# kicker.net
KiCad netlist of a schematic drawn in EAGLE
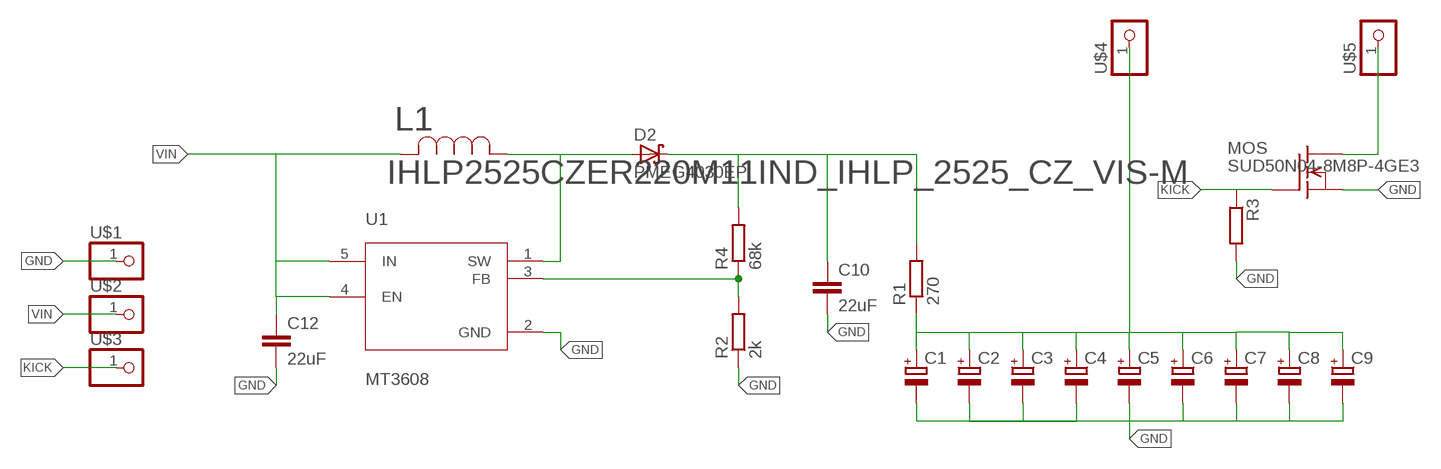
[diagram p0: schematic, sheet 1]

(export (version "E")
  (design (tool "Eeschema 10.0.6"))
  (components
    (comp (ref "C1")
      (value "CPOL-EU153CLV-1010")
      (footprint "eagle-import:153CLV-1010")
      (libsource (lib "eagle-import") (part "CPOL-EU153CLV-1010"))
    )
    (comp (ref "C2")
      (value "CPOL-EU153CLV-1010")
      (footprint "eagle-import:153CLV-1010")
      (libsource (lib "eagle-import") (part "CPOL-EU153CLV-1010"))
    )
    (comp (ref "C3")
      (value "CPOL-EU153CLV-1010")
      (footprint "eagle-import:153CLV-1010")
      (libsource (lib "eagle-import") (part "CPOL-EU153CLV-1010"))
    )
    (comp (ref "C4")
      (value "CPOL-EU153CLV-1010")
      (footprint "eagle-import:153CLV-1010")
      (libsource (lib "eagle-import") (part "CPOL-EU153CLV-1010"))
    )
    (comp (ref "C5")
      (value "CPOL-EU153CLV-1010")
      (footprint "eagle-import:153CLV-1010")
      (libsource (lib "eagle-import") (part "CPOL-EU153CLV-1010"))
    )
    (comp (ref "C6")
      (value "CPOL-EU153CLV-1010")
      (footprint "eagle-import:153CLV-1010")
      (libsource (lib "eagle-import") (part "CPOL-EU153CLV-1010"))
    )
    (comp (ref "C7")
      (value "CPOL-EU153CLV-1010")
      (footprint "eagle-import:153CLV-1010")
      (libsource (lib "eagle-import") (part "CPOL-EU153CLV-1010"))
    )
    (comp (ref "C8")
      (value "CPOL-EU153CLV-1010")
      (footprint "eagle-import:153CLV-1010")
      (libsource (lib "eagle-import") (part "CPOL-EU153CLV-1010"))
    )
    (comp (ref "C9")
      (value "CPOL-EU153CLV-1010")
      (footprint "eagle-import:153CLV-1010")
      (libsource (lib "eagle-import") (part "CPOL-EU153CLV-1010"))
    )
    (comp (ref "C10")
      (value "22uF")
      (footprint "eagle-import:C0805")
      (libsource (lib "eagle-import") (part "C-EUC0805"))
    )
    (comp (ref "C12")
      (value "22uF")
      (footprint "eagle-import:C0805")
      (libsource (lib "eagle-import") (part "C-EUC0805"))
    )
    (comp (ref "D2")
      (value "PMEG4030EP")
      (footprint "eagle-import:SOD128")
      (libsource (lib "eagle-import") (part "PMEG4030EP"))
    )
    (comp (ref "L1")
      (value "IHLP2525CZER220M11IND_IHLP_2525_CZ_VIS-M")
      (footprint "eagle-import:IND_IHLP_2525_CZ_VIS-M")
      (fields (field (name "MANUFACTURER_PART_NUMBER") "IHLP2525CZER220M11"))
      (libsource (lib "eagle-import") (part "IHLP2525CZER220M11IND_IHLP_2525_CZ_VIS-M"))
    )
    (comp (ref "MOS")
      (value "SUD50N04-8M8P-4GE3")
      (footprint "eagle-import:TO252")
      (libsource (lib "eagle-import") (part "SUD50N04-8M8P-4GE3"))
    )
    (comp (ref "R1")
      (value "270")
      (footprint "eagle-import:R2010")
      (libsource (lib "eagle-import") (part "R-EU_R2010"))
    )
    (comp (ref "R2")
      (value "2k")
      (footprint "eagle-import:M0805")
      (libsource (lib "eagle-import") (part "resistor_R-EU_M0805"))
    )
    (comp (ref "R3")
      (value "R-EU_M0805")
      (footprint "eagle-import:M0805")
      (libsource (lib "eagle-import") (part "resistor_R-EU_M0805"))
    )
    (comp (ref "R4")
      (value "68k")
      (footprint "eagle-import:M0805")
      (libsource (lib "eagle-import") (part "resistor_R-EU_M0805"))
    )
    (comp (ref "U$1")
      (value "CONNEC_1X01PAD")
      (footprint "eagle-import:1_PAD")
      (libsource (lib "eagle-import") (part "CONNEC_1X01PAD"))
    )
    (comp (ref "U$2")
      (value "CONNEC_1X01PAD")
      (footprint "eagle-import:1_PAD")
      (libsource (lib "eagle-import") (part "CONNEC_1X01PAD"))
    )
    (comp (ref "U$3")
      (value "CONNEC_1X01PAD")
      (footprint "eagle-import:1_PAD")
      (libsource (lib "eagle-import") (part "CONNEC_1X01PAD"))
    )
    (comp (ref "U$4")
      (value "CONNEC_1X01PAD")
      (footprint "eagle-import:1_PAD")
      (libsource (lib "eagle-import") (part "CONNEC_1X01PAD"))
    )
    (comp (ref "U$5")
      (value "CONNEC_1X01PAD")
      (footprint "eagle-import:1_PAD")
      (libsource (lib "eagle-import") (part "CONNEC_1X01PAD"))
    )
    (comp (ref "U1")
      (value "MT3608")
      (footprint "eagle-import:SOT95P280X145-6N")
      (fields (field (name "MF") "Aerosemi Technology Co., Ltd"))
      (libsource (lib "eagle-import") (part "MT3608"))
    )
  )
  (nets
    (net (code "1") (name "GND") (class "Default")
      (node (ref "C1") (pin "-") (pinfunction "-_-") (pintype "passive"))
      (node (ref "C10") (pin "2") (pinfunction "2_2") (pintype "passive"))
      (node (ref "C12") (pin "2") (pinfunction "2_2") (pintype "passive"))
      (node (ref "C2") (pin "-") (pinfunction "-_-") (pintype "passive"))
      (node (ref "C3") (pin "-") (pinfunction "-_-") (pintype "passive"))
      (node (ref "C4") (pin "-") (pinfunction "-_-") (pintype "passive"))
      (node (ref "C5") (pin "-") (pinfunction "-_-") (pintype "passive"))
      (node (ref "C6") (pin "-") (pinfunction "-_-") (pintype "passive"))
      (node (ref "C7") (pin "-") (pinfunction "-_-") (pintype "passive"))
      (node (ref "C8") (pin "-") (pinfunction "-_-") (pintype "passive"))
      (node (ref "C9") (pin "-") (pinfunction "-_-") (pintype "passive"))
      (node (ref "MOS") (pin "2") (pinfunction "S_2") (pintype "passive"))
      (node (ref "R2") (pin "1") (pinfunction "1_1") (pintype "passive"))
      (node (ref "R3") (pin "2") (pinfunction "2_2") (pintype "passive"))
      (node (ref "U$1") (pin "1") (pinfunction "1_1") (pintype "passive"))
      (node (ref "U1") (pin "2") (pinfunction "GND_2") (pintype "power_in"))
    )
    (net (code "2") (name "KICK") (class "Default")
      (node (ref "MOS") (pin "1") (pinfunction "G_1") (pintype "passive"))
      (node (ref "R3") (pin "1") (pinfunction "1_1") (pintype "passive"))
      (node (ref "U$3") (pin "1") (pinfunction "1_1") (pintype "passive"))
    )
    (net (code "3") (name "Net-(C1-Pad+)") (class "Default")
      (node (ref "C1") (pin "+") (pinfunction "+_+") (pintype "passive"))
      (node (ref "C2") (pin "+") (pinfunction "+_+") (pintype "passive"))
      (node (ref "C3") (pin "+") (pinfunction "+_+") (pintype "passive"))
      (node (ref "C4") (pin "+") (pinfunction "+_+") (pintype "passive"))
      (node (ref "C5") (pin "+") (pinfunction "+_+") (pintype "passive"))
      (node (ref "C6") (pin "+") (pinfunction "+_+") (pintype "passive"))
      (node (ref "C7") (pin "+") (pinfunction "+_+") (pintype "passive"))
      (node (ref "C8") (pin "+") (pinfunction "+_+") (pintype "passive"))
      (node (ref "C9") (pin "+") (pinfunction "+_+") (pintype "passive"))
      (node (ref "R1") (pin "1") (pinfunction "1_1") (pintype "passive"))
      (node (ref "U$4") (pin "1") (pinfunction "1_1") (pintype "passive"))
    )
    (net (code "4") (name "Net-(D2-A)") (class "Default")
      (node (ref "D2") (pin "2") (pinfunction "A_2") (pintype "passive"))
      (node (ref "L1") (pin "1") (pinfunction "1_1") (pintype "passive"))
      (node (ref "U1") (pin "1") (pinfunction "SW_1") (pintype "output"))
    )
    (net (code "5") (name "Net-(D2-K)") (class "Default")
      (node (ref "C10") (pin "1") (pinfunction "1_1") (pintype "passive"))
      (node (ref "D2") (pin "1") (pinfunction "K_1") (pintype "passive"))
      (node (ref "R1") (pin "2") (pinfunction "2_2") (pintype "passive"))
      (node (ref "R4") (pin "2") (pinfunction "2_2") (pintype "passive"))
    )
    (net (code "6") (name "Net-(MOS-D)") (class "Default")
      (node (ref "MOS") (pin "3") (pinfunction "D_3") (pintype "passive"))
      (node (ref "U$5") (pin "1") (pinfunction "1_1") (pintype "passive"))
    )
    (net (code "7") (name "Net-(U1-FB)") (class "Default")
      (node (ref "R2") (pin "2") (pinfunction "2_2") (pintype "passive"))
      (node (ref "R4") (pin "1") (pinfunction "1_1") (pintype "passive"))
      (node (ref "U1") (pin "3") (pinfunction "FB_3") (pintype "input"))
    )
    (net (code "8") (name "VIN") (class "Default")
      (node (ref "C12") (pin "1") (pinfunction "1_1") (pintype "passive"))
      (node (ref "L1") (pin "2") (pinfunction "2_2") (pintype "passive"))
      (node (ref "U$2") (pin "1") (pinfunction "1_1") (pintype "passive"))
      (node (ref "U1") (pin "4") (pinfunction "EN_4") (pintype "input"))
      (node (ref "U1") (pin "5") (pinfunction "IN_5") (pintype "input"))
    )
  )
)
